# interface_board.net
KiCad netlist of a schematic drawn in EAGLE
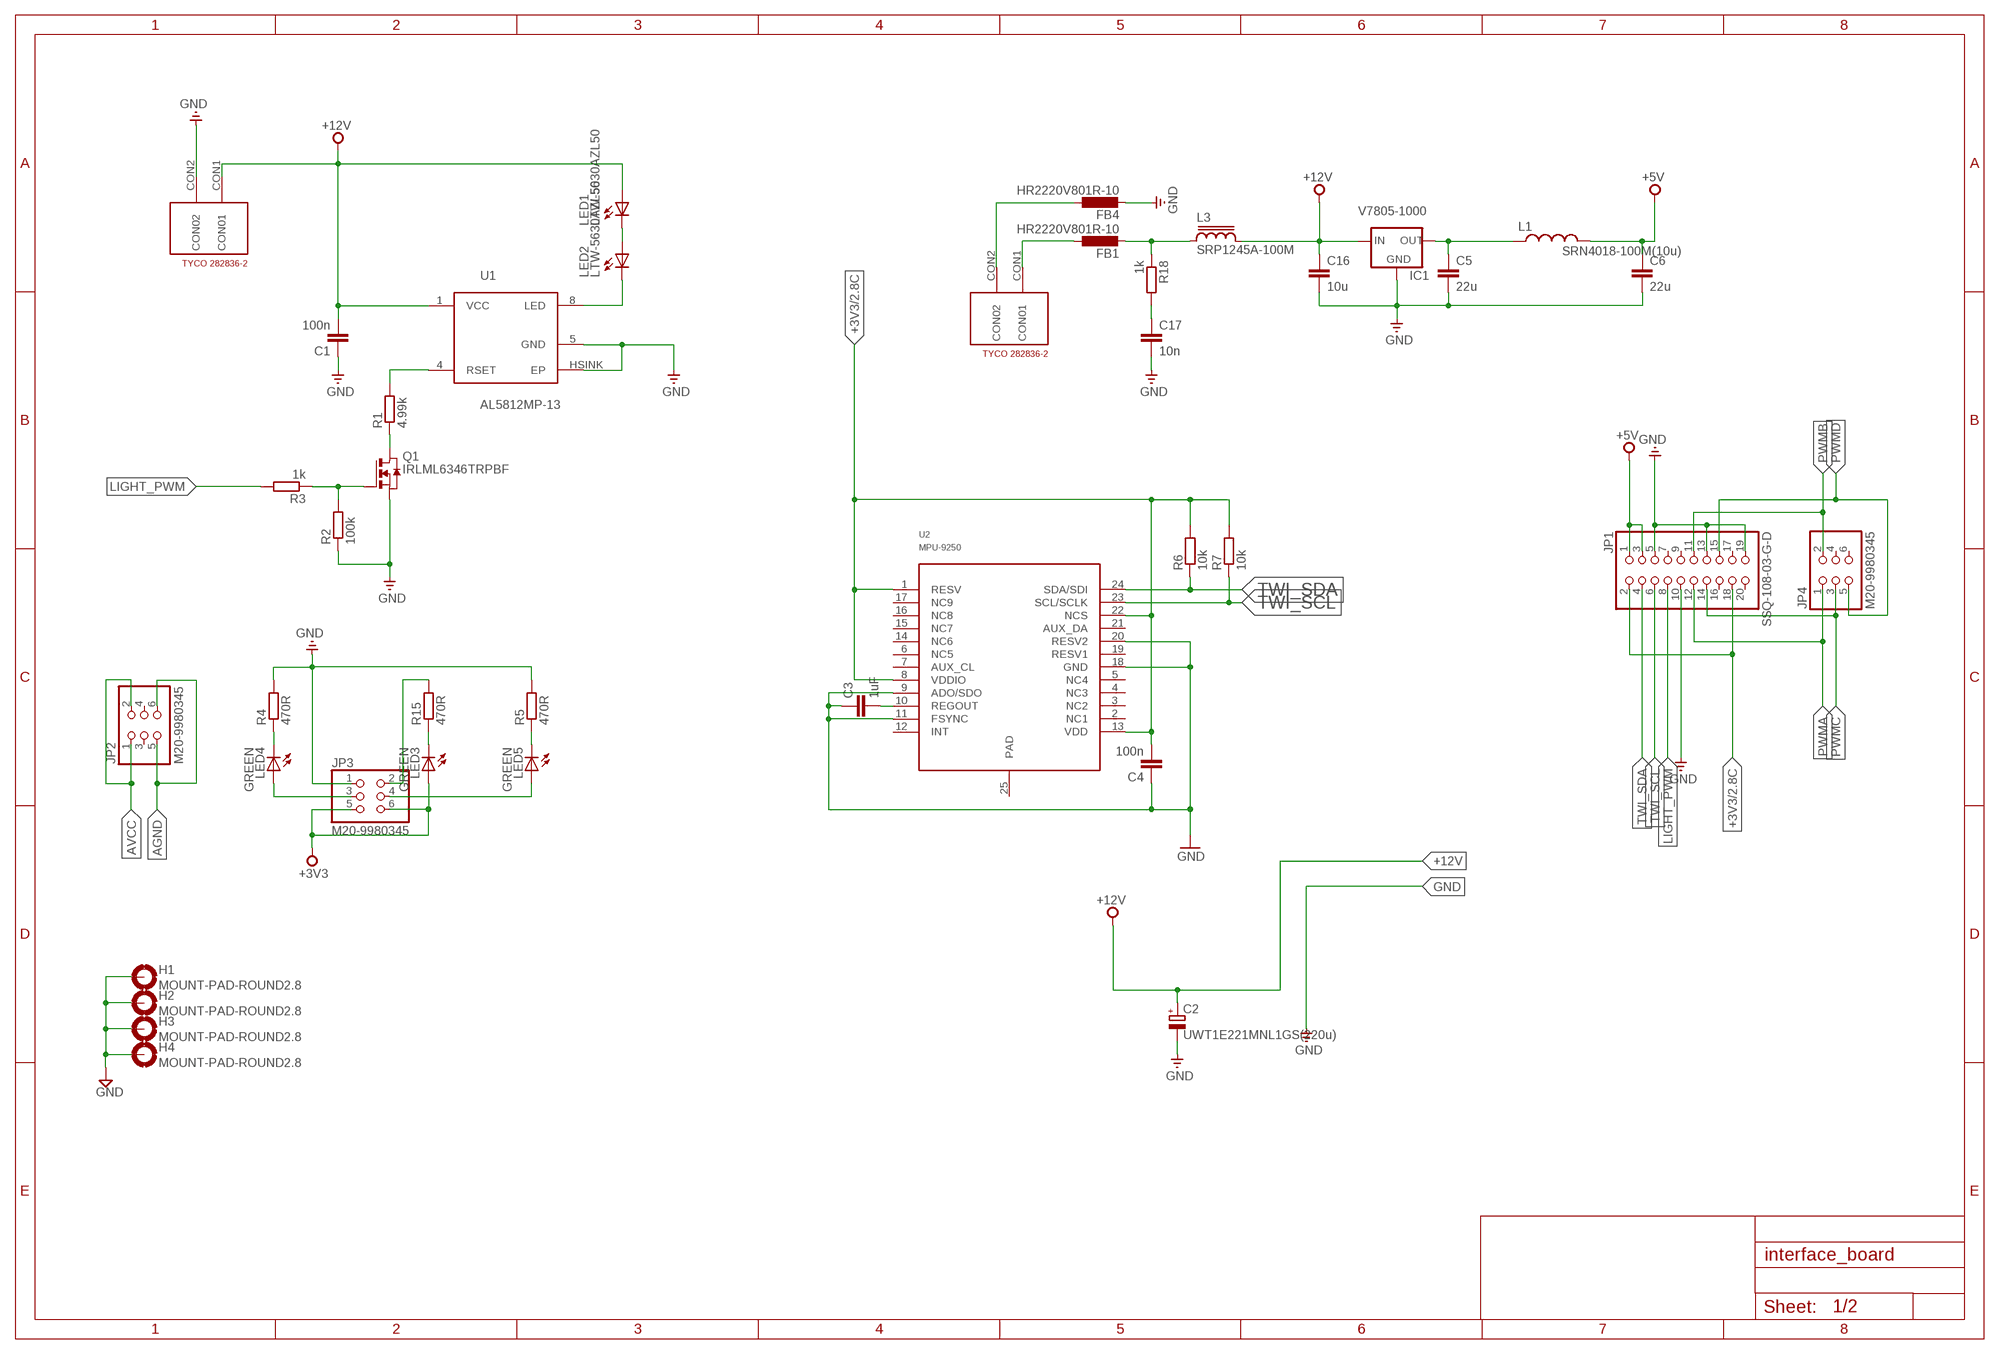
[diagram p0: schematic, sheet 1]
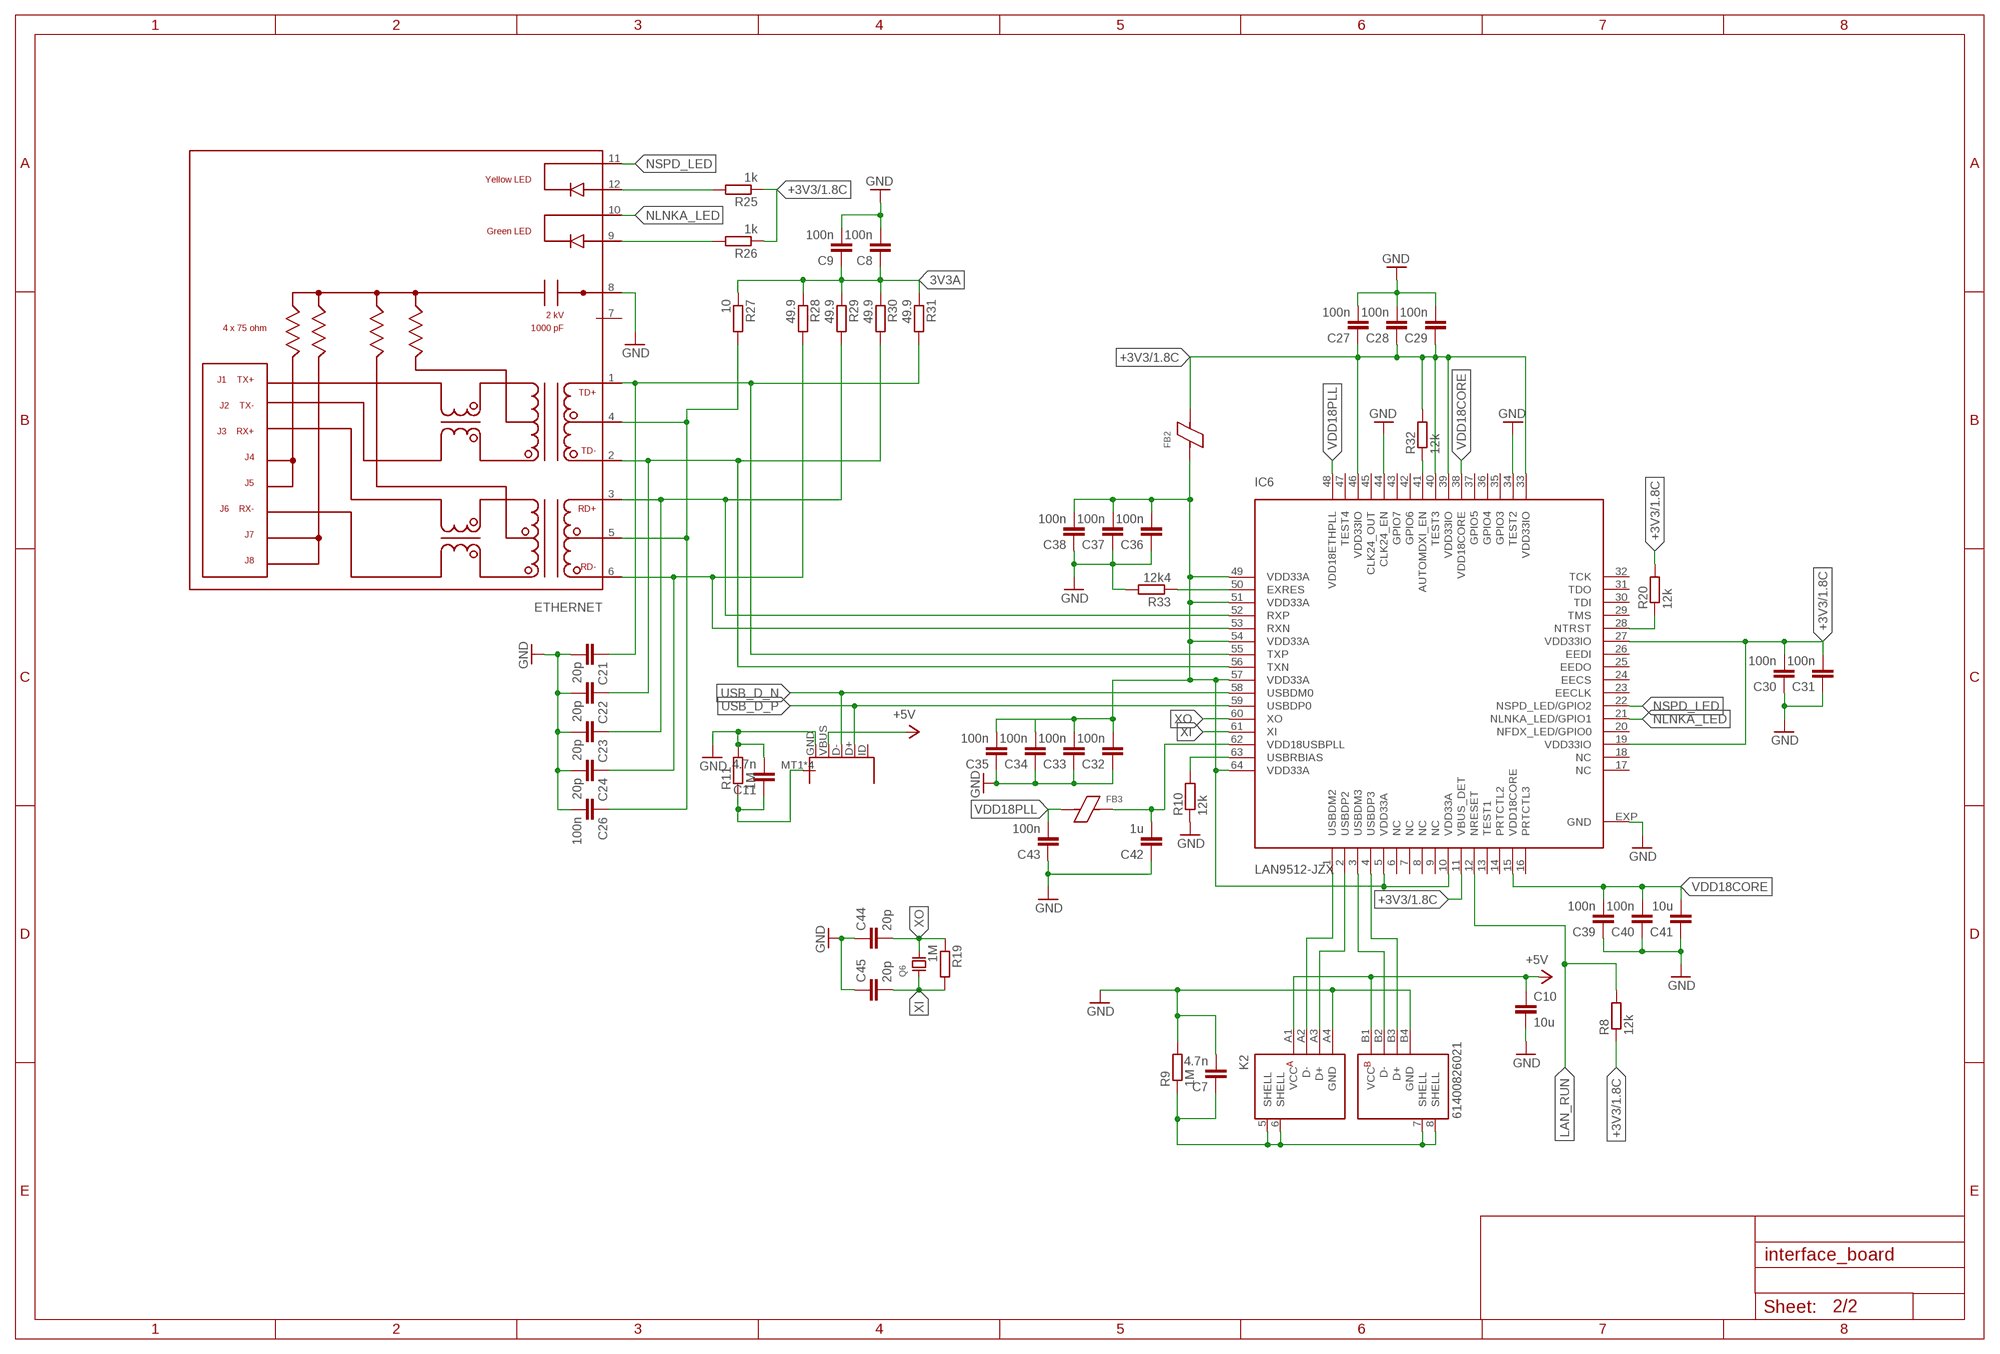
[diagram p1: schematic, sheet 2]

(export (version "E")
  (design (tool "Eeschema 10.0.6"))
  (components
    (comp (ref "C7")
      (value "4.7n")
      (footprint "eagle-import:C0402")
      (libsource (lib "eagle-import") (part "C-EUC0402"))
    )
    (comp (ref "C8")
      (value "100n")
      (footprint "eagle-import:C0402")
      (libsource (lib "eagle-import") (part "C-EUC0402"))
    )
    (comp (ref "C9")
      (value "100n")
      (footprint "eagle-import:C0402")
      (libsource (lib "eagle-import") (part "C-EUC0402"))
    )
    (comp (ref "C10")
      (value "10u")
      (footprint "eagle-import:C0603")
      (libsource (lib "eagle-import") (part "C-EUC0603"))
    )
    (comp (ref "C11")
      (value "4.7n")
      (footprint "eagle-import:C0402")
      (libsource (lib "eagle-import") (part "C-EUC0402"))
    )
    (comp (ref "C21")
      (value "20p")
      (footprint "eagle-import:C0402")
      (libsource (lib "eagle-import") (part "C-EUC0402"))
    )
    (comp (ref "C22")
      (value "20p")
      (footprint "eagle-import:C0402")
      (libsource (lib "eagle-import") (part "C-EUC0402"))
    )
    (comp (ref "C23")
      (value "20p")
      (footprint "eagle-import:C0402")
      (libsource (lib "eagle-import") (part "C-EUC0402"))
    )
    (comp (ref "C24")
      (value "20p")
      (footprint "eagle-import:C0402")
      (libsource (lib "eagle-import") (part "C-EUC0402"))
    )
    (comp (ref "C26")
      (value "100n")
      (footprint "eagle-import:C0402")
      (libsource (lib "eagle-import") (part "C-EUC0402"))
    )
    (comp (ref "C27")
      (value "100n")
      (footprint "eagle-import:C0402")
      (libsource (lib "eagle-import") (part "C-EUC0402"))
    )
    (comp (ref "C28")
      (value "100n")
      (footprint "eagle-import:C0402")
      (libsource (lib "eagle-import") (part "C-EUC0402"))
    )
    (comp (ref "C29")
      (value "100n")
      (footprint "eagle-import:C0402")
      (libsource (lib "eagle-import") (part "C-EUC0402"))
    )
    (comp (ref "C30")
      (value "100n")
      (footprint "eagle-import:C0402")
      (libsource (lib "eagle-import") (part "C-EUC0402"))
    )
    (comp (ref "C31")
      (value "100n")
      (footprint "eagle-import:C0402")
      (libsource (lib "eagle-import") (part "C-EUC0402"))
    )
    (comp (ref "C32")
      (value "100n")
      (footprint "eagle-import:C0402")
      (libsource (lib "eagle-import") (part "C-EUC0402"))
    )
    (comp (ref "C33")
      (value "100n")
      (footprint "eagle-import:C0402")
      (libsource (lib "eagle-import") (part "C-EUC0402"))
    )
    (comp (ref "C34")
      (value "100n")
      (footprint "eagle-import:C0402")
      (libsource (lib "eagle-import") (part "C-EUC0402"))
    )
    (comp (ref "C35")
      (value "100n")
      (footprint "eagle-import:C0402")
      (libsource (lib "eagle-import") (part "C-EUC0402"))
    )
    (comp (ref "C36")
      (value "100n")
      (footprint "eagle-import:C0402")
      (libsource (lib "eagle-import") (part "C-EUC0402"))
    )
    (comp (ref "C37")
      (value "100n")
      (footprint "eagle-import:C0402")
      (libsource (lib "eagle-import") (part "C-EUC0402"))
    )
    (comp (ref "C38")
      (value "100n")
      (footprint "eagle-import:C0402")
      (libsource (lib "eagle-import") (part "C-EUC0402"))
    )
    (comp (ref "C39")
      (value "100n")
      (footprint "eagle-import:C0402")
      (libsource (lib "eagle-import") (part "C-EUC0402"))
    )
    (comp (ref "C40")
      (value "100n")
      (footprint "eagle-import:C0402")
      (libsource (lib "eagle-import") (part "C-EUC0402"))
    )
    (comp (ref "C41")
      (value "10u")
      (footprint "eagle-import:C0603")
      (libsource (lib "eagle-import") (part "C-EUC0603"))
    )
    (comp (ref "C42")
      (value "1u")
      (footprint "eagle-import:C0402")
      (libsource (lib "eagle-import") (part "C-EUC0402"))
    )
    (comp (ref "C43")
      (value "100n")
      (footprint "eagle-import:C0402")
      (libsource (lib "eagle-import") (part "C-EUC0402"))
    )
    (comp (ref "C44")
      (value "20p")
      (footprint "eagle-import:C0402")
      (libsource (lib "eagle-import") (part "C-EUC0402"))
    )
    (comp (ref "C45")
      (value "20p")
      (footprint "eagle-import:C0402")
      (libsource (lib "eagle-import") (part "C-EUC0402"))
    )
    (comp (ref "ETHERNET")
      (value "HR911105A")
      (footprint "eagle-import:RJ45")
      (libsource (lib "eagle-import") (part "HR911105A"))
    )
    (comp (ref "FB2")
      (value "742792022")
      (footprint "eagle-import:C0805")
      (libsource (lib "eagle-import") (part "FERRITE_BEAD"))
    )
    (comp (ref "FB3")
      (value "742792022")
      (footprint "eagle-import:C0805")
      (libsource (lib "eagle-import") (part "FERRITE_BEAD"))
    )
    (comp (ref "IC6")
      (value "LAN9512-JZX")
      (footprint "eagle-import:QFN64-9X9")
      (libsource (lib "eagle-import") (part "LAN9512"))
    )
    (comp (ref "JP6")
      (value "10118192-0001LF")
      (footprint "eagle-import:USB-MICRO")
      (libsource (lib "eagle-import") (part "USB-IDMICRO"))
    )
    (comp (ref "K2")
      (value "61400826021")
      (footprint "eagle-import:61400826021")
      (libsource (lib "eagle-import") (part "61400826021"))
    )
    (comp (ref "Q6")
      (value "FA-238 25.0000MB")
      (footprint "eagle-import:CTS_32X25")
      (libsource (lib "eagle-import") (part "CTS_32X25_SMD"))
    )
    (comp (ref "R8")
      (value "12k")
      (footprint "eagle-import:R0402")
      (libsource (lib "eagle-import") (part "R-EU_R0402"))
    )
    (comp (ref "R9")
      (value "1M")
      (footprint "eagle-import:R0402")
      (libsource (lib "eagle-import") (part "R-EU_R0402"))
    )
    (comp (ref "R10")
      (value "12k")
      (footprint "eagle-import:R0402")
      (libsource (lib "eagle-import") (part "R-EU_R0402"))
    )
    (comp (ref "R11")
      (value "1M")
      (footprint "eagle-import:R0402")
      (libsource (lib "eagle-import") (part "R-EU_R0402"))
    )
    (comp (ref "R19")
      (value "1M")
      (footprint "eagle-import:R0402")
      (libsource (lib "eagle-import") (part "R-EU_R0402"))
    )
    (comp (ref "R20")
      (value "12k")
      (footprint "eagle-import:R0402")
      (libsource (lib "eagle-import") (part "R-EU_R0402"))
    )
    (comp (ref "R25")
      (value "1k")
      (footprint "eagle-import:R0402")
      (libsource (lib "eagle-import") (part "R-EU_R0402"))
    )
    (comp (ref "R26")
      (value "1k")
      (footprint "eagle-import:R0402")
      (libsource (lib "eagle-import") (part "R-EU_R0402"))
    )
    (comp (ref "R27")
      (value "10")
      (footprint "eagle-import:R0402")
      (libsource (lib "eagle-import") (part "R-EU_R0402"))
    )
    (comp (ref "R28")
      (value "49.9")
      (footprint "eagle-import:R0402")
      (libsource (lib "eagle-import") (part "R-EU_R0402"))
    )
    (comp (ref "R29")
      (value "49.9")
      (footprint "eagle-import:R0402")
      (libsource (lib "eagle-import") (part "R-EU_R0402"))
    )
    (comp (ref "R30")
      (value "49.9")
      (footprint "eagle-import:R0402")
      (libsource (lib "eagle-import") (part "R-EU_R0402"))
    )
    (comp (ref "R31")
      (value "49.9")
      (footprint "eagle-import:R0402")
      (libsource (lib "eagle-import") (part "R-EU_R0402"))
    )
    (comp (ref "R32")
      (value "12k")
      (footprint "eagle-import:R0402")
      (libsource (lib "eagle-import") (part "R-EU_R0402"))
    )
    (comp (ref "R33")
      (value "12k4")
      (footprint "eagle-import:R0402")
      (libsource (lib "eagle-import") (part "R-EU_R0402"))
    )
    (comp (ref "C1")
      (value "100n")
      (footprint "eagle-import:C0402")
      (libsource (lib "eagle-import") (part "C-EUC0402"))
    )
    (comp (ref "C2")
      (value "UWT1E221MNL1GS(220u)")
      (footprint "eagle-import:153CLV-0810")
      (libsource (lib "eagle-import") (part "CPOL-EU153CLV-0810"))
    )
    (comp (ref "C3")
      (value "1uF")
      (footprint "eagle-import:C0402")
      (libsource (lib "eagle-import") (part "C-EUC0402"))
    )
    (comp (ref "C4")
      (value "100n")
      (footprint "eagle-import:C0402")
      (libsource (lib "eagle-import") (part "C-EUC0402"))
    )
    (comp (ref "C5")
      (value "22u")
      (footprint "eagle-import:C0603")
      (libsource (lib "eagle-import") (part "C-EUC0603"))
    )
    (comp (ref "C6")
      (value "22u")
      (footprint "eagle-import:C0603")
      (libsource (lib "eagle-import") (part "C-EUC0603"))
    )
    (comp (ref "C16")
      (value "10u")
      (footprint "eagle-import:C0603")
      (libsource (lib "eagle-import") (part "C-EUC0603"))
    )
    (comp (ref "C17")
      (value "10n")
      (footprint "eagle-import:C0402")
      (libsource (lib "eagle-import") (part "C-EUC0402"))
    )
    (comp (ref "FB1")
      (value "HR2220V801R-10")
      (footprint "eagle-import:L5650M")
      (libsource (lib "eagle-import") (part "L-EUL5650M"))
    )
    (comp (ref "FB4")
      (value "HR2220V801R-10")
      (footprint "eagle-import:L5650M")
      (libsource (lib "eagle-import") (part "L-EUL5650M"))
    )
    (comp (ref "H1")
      (value "MOUNT-PAD-ROUND2.8")
      (footprint "eagle-import:2,8-PAD")
      (libsource (lib "eagle-import") (part "MOUNT-PAD-ROUND2.8"))
    )
    (comp (ref "H2")
      (value "MOUNT-PAD-ROUND2.8")
      (footprint "eagle-import:2,8-PAD")
      (libsource (lib "eagle-import") (part "MOUNT-PAD-ROUND2.8"))
    )
    (comp (ref "H3")
      (value "MOUNT-PAD-ROUND2.8")
      (footprint "eagle-import:2,8-PAD")
      (libsource (lib "eagle-import") (part "MOUNT-PAD-ROUND2.8"))
    )
    (comp (ref "H4")
      (value "MOUNT-PAD-ROUND2.8")
      (footprint "eagle-import:2,8-PAD")
      (libsource (lib "eagle-import") (part "MOUNT-PAD-ROUND2.8"))
    )
    (comp (ref "IC1")
      (value "V7805-1000")
      (footprint "eagle-import:DIP_3PIN")
      (libsource (lib "eagle-import") (part "VR_1OUTXX"))
    )
    (comp (ref "JP1")
      (value "SSQ-108-03-G-D")
      (footprint "eagle-import:2X10")
      (libsource (lib "eagle-import") (part "PINHD-2X10"))
    )
    (comp (ref "JP2")
      (value "M20-9980345")
      (footprint "eagle-import:2X03")
      (libsource (lib "eagle-import") (part "PINHD-2X3"))
    )
    (comp (ref "JP3")
      (value "M20-9980345")
      (footprint "eagle-import:2X03")
      (libsource (lib "eagle-import") (part "PINHD-2X3"))
    )
    (comp (ref "JP4")
      (value "M20-9980345")
      (footprint "eagle-import:2X03")
      (libsource (lib "eagle-import") (part "PINHD-2X3"))
    )
    (comp (ref "L1")
      (value "SRN4018-100M(10u)")
      (footprint "eagle-import:BOURNS-SRN4018")
      (libsource (lib "eagle-import") (part "BOURNS-SRN4018"))
    )
    (comp (ref "L3")
      (value "SRP1245A-100M")
      (footprint "eagle-import:SRP1250A")
      (libsource (lib "eagle-import") (part "SRP1250A"))
    )
    (comp (ref "LED1")
      (value "LTW-5630AZL50")
      (footprint "eagle-import:LITEON-5630")
      (libsource (lib "eagle-import") (part "LTW-5630AZL"))
    )
    (comp (ref "LED2")
      (value "LTW-5630AZL50")
      (footprint "eagle-import:LITEON-5630")
      (libsource (lib "eagle-import") (part "LTW-5630AZL"))
    )
    (comp (ref "LED3")
      (value "GREEN")
      (footprint "eagle-import:CHIP-LED0603")
      (libsource (lib "eagle-import") (part "LEDCHIP-LED0603"))
    )
    (comp (ref "LED4")
      (value "GREEN")
      (footprint "eagle-import:CHIP-LED0603")
      (libsource (lib "eagle-import") (part "LEDCHIP-LED0603"))
    )
    (comp (ref "LED5")
      (value "GREEN")
      (footprint "eagle-import:CHIP-LED0603")
      (libsource (lib "eagle-import") (part "LEDCHIP-LED0603"))
    )
    (comp (ref "Q1")
      (value "IRLML6346TRPBF")
      (footprint "eagle-import:SOT23")
      (libsource (lib "eagle-import") (part "NMOS-FETSOT23"))
    )
    (comp (ref "R1")
      (value "4.99k")
      (footprint "eagle-import:R0402")
      (libsource (lib "eagle-import") (part "R-EU_R0402"))
    )
    (comp (ref "R2")
      (value "100k")
      (footprint "eagle-import:R0402")
      (libsource (lib "eagle-import") (part "R-EU_R0402"))
    )
    (comp (ref "R3")
      (value "1k")
      (footprint "eagle-import:R0402")
      (libsource (lib "eagle-import") (part "R-EU_R0402"))
    )
    (comp (ref "R4")
      (value "470R")
      (footprint "eagle-import:R0402")
      (libsource (lib "eagle-import") (part "R-EU_R0402"))
    )
    (comp (ref "R5")
      (value "470R")
      (footprint "eagle-import:R0402")
      (libsource (lib "eagle-import") (part "R-EU_R0402"))
    )
    (comp (ref "R6")
      (value "10k")
      (footprint "eagle-import:R0402")
      (libsource (lib "eagle-import") (part "R-EU_R0402"))
    )
    (comp (ref "R7")
      (value "10k")
      (footprint "eagle-import:R0402")
      (libsource (lib "eagle-import") (part "R-EU_R0402"))
    )
    (comp (ref "R15")
      (value "470R")
      (footprint "eagle-import:R0402")
      (libsource (lib "eagle-import") (part "R-EU_R0402"))
    )
    (comp (ref "R18")
      (value "1k")
      (footprint "eagle-import:R0402")
      (libsource (lib "eagle-import") (part "R-EU_R0402"))
    )
    (comp (ref "U$2")
      (value "282836-2")
      (footprint "eagle-import:282836-2")
      (libsource (lib "eagle-import") (part "282836-2"))
    )
    (comp (ref "U$4")
      (value "282836-2")
      (footprint "eagle-import:282836-2")
      (libsource (lib "eagle-import") (part "282836-2"))
    )
    (comp (ref "U1")
      (value "AL5812MP-13")
      (footprint "eagle-import:MSOP-8EP")
      (libsource (lib "eagle-import") (part "AL5812MP-13"))
    )
    (comp (ref "U2")
      (value "MPU-9250")
      (footprint "eagle-import:LEAD-QFN24")
      (libsource (lib "eagle-import") (part "MPU-9250"))
    )
  )
  (nets
    (net (code "1") (name "+3V3") (class "Default")
      (node (ref "C27") (pin "1") (pinfunction "1_1") (pintype "passive"))
      (node (ref "C28") (pin "1") (pinfunction "1_1") (pintype "passive"))
      (node (ref "C29") (pin "1") (pinfunction "1_1") (pintype "passive"))
      (node (ref "C30") (pin "2") (pinfunction "2_2") (pintype "passive"))
      (node (ref "C31") (pin "2") (pinfunction "2_2") (pintype "passive"))
      (node (ref "C4") (pin "2") (pinfunction "2_2") (pintype "passive"))
      (node (ref "FB2") (pin "2") (pinfunction "P$2_2") (pintype "bidirectional"))
      (node (ref "IC6") (pin "11") (pinfunction "VBUS_DET_11") (pintype "bidirectional"))
      (node (ref "IC6") (pin "19") (pinfunction "VDD33IO_19") (pintype "bidirectional"))
      (node (ref "IC6") (pin "27") (pinfunction "VDD33IO_27") (pintype "bidirectional"))
      (node (ref "IC6") (pin "33") (pinfunction "VDD33IO_33") (pintype "bidirectional"))
      (node (ref "IC6") (pin "39") (pinfunction "VDD33IO_39") (pintype "bidirectional"))
      (node (ref "IC6") (pin "40") (pinfunction "TEST3_40") (pintype "bidirectional"))
      (node (ref "IC6") (pin "46") (pinfunction "VDD33IO_46") (pintype "bidirectional"))
      (node (ref "JP1") (pin "18") (pinfunction "18_18") (pintype "passive"))
      (node (ref "JP1") (pin "2") (pinfunction "2_2") (pintype "passive"))
      (node (ref "JP3") (pin "5") (pinfunction "5_5") (pintype "passive"))
      (node (ref "JP3") (pin "6") (pinfunction "6_6") (pintype "passive"))
      (node (ref "LED3") (pin "A") (pinfunction "A_A") (pintype "passive"))
      (node (ref "R20") (pin "2") (pinfunction "2_2") (pintype "passive"))
      (node (ref "R25") (pin "1") (pinfunction "1_1") (pintype "passive"))
      (node (ref "R26") (pin "1") (pinfunction "1_1") (pintype "passive"))
      (node (ref "R32") (pin "2") (pinfunction "2_2") (pintype "passive"))
      (node (ref "R6") (pin "2") (pinfunction "2_2") (pintype "passive"))
      (node (ref "R7") (pin "2") (pinfunction "2_2") (pintype "passive"))
      (node (ref "R8") (pin "1") (pinfunction "1_1") (pintype "passive"))
      (node (ref "U2") (pin "1") (pinfunction "RESV_1") (pintype "bidirectional"))
      (node (ref "U2") (pin "13") (pinfunction "VDD_13") (pintype "bidirectional"))
      (node (ref "U2") (pin "22") (pinfunction "NCS_22") (pintype "bidirectional"))
      (node (ref "U2") (pin "8") (pinfunction "VDDIO_8") (pintype "bidirectional"))
    )
    (net (code "2") (name "+5V") (class "Default")
      (node (ref "C10") (pin "1") (pinfunction "1_1") (pintype "passive"))
      (node (ref "C6") (pin "1") (pinfunction "1_1") (pintype "passive"))
      (node (ref "JP1") (pin "1") (pinfunction "1_1") (pintype "passive"))
      (node (ref "JP1") (pin "3") (pinfunction "3_3") (pintype "passive"))
      (node (ref "JP6") (pin "VBUS") (pinfunction "VBUS_VBUS") (pintype "bidirectional"))
      (node (ref "K2") (pin "A1") (pinfunction "VCC_A1") (pintype "bidirectional"))
      (node (ref "K2") (pin "B1") (pinfunction "VCC_B1") (pintype "bidirectional"))
      (node (ref "L1") (pin "P$1") (pinfunction "1_P$1") (pintype "passive"))
    )
    (net (code "3") (name "+12V") (class "Default")
      (node (ref "C1") (pin "2") (pinfunction "2_2") (pintype "passive"))
      (node (ref "C16") (pin "1") (pinfunction "1_1") (pintype "passive"))
      (node (ref "C2") (pin "+") (pinfunction "+_+") (pintype "passive"))
      (node (ref "IC1") (pin "IN") (pinfunction "IN_IN") (pintype "input"))
      (node (ref "L3") (pin "2") (pinfunction "2_2") (pintype "passive"))
      (node (ref "LED1") (pin "A1") (pinfunction "A_A1") (pintype "passive"))
      (node (ref "LED1") (pin "A2") (pinfunction "A_A2") (pintype "passive"))
      (node (ref "LED1") (pin "A3") (pinfunction "A_A3") (pintype "passive"))
      (node (ref "U$4") (pin "CON1") (pinfunction "CON01_CON1") (pintype "bidirectional"))
      (node (ref "U1") (pin "1") (pinfunction "VCC_1") (pintype "bidirectional"))
    )
    (net (code "4") (name "3V3A") (class "Default")
      (node (ref "C32") (pin "2") (pinfunction "2_2") (pintype "passive"))
      (node (ref "C33") (pin "2") (pinfunction "2_2") (pintype "passive"))
      (node (ref "C34") (pin "2") (pinfunction "2_2") (pintype "passive"))
      (node (ref "C35") (pin "2") (pinfunction "2_2") (pintype "passive"))
      (node (ref "C36") (pin "2") (pinfunction "2_2") (pintype "passive"))
      (node (ref "C37") (pin "2") (pinfunction "2_2") (pintype "passive"))
      (node (ref "C38") (pin "2") (pinfunction "2_2") (pintype "passive"))
      (node (ref "C8") (pin "1") (pinfunction "1_1") (pintype "passive"))
      (node (ref "C9") (pin "1") (pinfunction "1_1") (pintype "passive"))
      (node (ref "FB2") (pin "1") (pinfunction "P$1_1") (pintype "bidirectional"))
      (node (ref "IC6") (pin "10") (pinfunction "VDD33A_10") (pintype "bidirectional"))
      (node (ref "IC6") (pin "49") (pinfunction "VDD33A_49") (pintype "bidirectional"))
      (node (ref "IC6") (pin "5") (pinfunction "VDD33A_5") (pintype "bidirectional"))
      (node (ref "IC6") (pin "51") (pinfunction "VDD33A_51") (pintype "bidirectional"))
      (node (ref "IC6") (pin "54") (pinfunction "VDD33A_54") (pintype "bidirectional"))
      (node (ref "IC6") (pin "57") (pinfunction "VDD33A_57") (pintype "bidirectional"))
      (node (ref "IC6") (pin "64") (pinfunction "VDD33A_64") (pintype "bidirectional"))
      (node (ref "R27") (pin "1") (pinfunction "1_1") (pintype "passive"))
      (node (ref "R28") (pin "1") (pinfunction "1_1") (pintype "passive"))
      (node (ref "R29") (pin "1") (pinfunction "1_1") (pintype "passive"))
      (node (ref "R30") (pin "1") (pinfunction "1_1") (pintype "passive"))
      (node (ref "R31") (pin "1") (pinfunction "1_1") (pintype "passive"))
    )
    (net (code "5") (name "AGND") (class "Default")
      (node (ref "FB4") (pin "1") (pinfunction "1_1") (pintype "passive"))
      (node (ref "JP2") (pin "5") (pinfunction "5_5") (pintype "passive"))
      (node (ref "JP2") (pin "6") (pinfunction "6_6") (pintype "passive"))
      (node (ref "U$2") (pin "CON2") (pinfunction "CON02_CON2") (pintype "bidirectional"))
    )
    (net (code "6") (name "AVCC") (class "Default")
      (node (ref "FB1") (pin "1") (pinfunction "1_1") (pintype "passive"))
      (node (ref "JP2") (pin "1") (pinfunction "1_1") (pintype "passive"))
      (node (ref "JP2") (pin "2") (pinfunction "2_2") (pintype "passive"))
      (node (ref "U$2") (pin "CON1") (pinfunction "CON01_CON1") (pintype "bidirectional"))
    )
    (net (code "7") (name "GND") (class "Default")
      (node (ref "C1") (pin "1") (pinfunction "1_1") (pintype "passive"))
      (node (ref "C10") (pin "2") (pinfunction "2_2") (pintype "passive"))
      (node (ref "C11") (pin "2") (pinfunction "2_2") (pintype "passive"))
      (node (ref "C16") (pin "2") (pinfunction "2_2") (pintype "passive"))
      (node (ref "C17") (pin "2") (pinfunction "2_2") (pintype "passive"))
      (node (ref "C2") (pin "-") (pinfunction "-_-") (pintype "passive"))
      (node (ref "C21") (pin "2") (pinfunction "2_2") (pintype "passive"))
      (node (ref "C22") (pin "2") (pinfunction "2_2") (pintype "passive"))
      (node (ref "C23") (pin "2") (pinfunction "2_2") (pintype "passive"))
      (node (ref "C24") (pin "2") (pinfunction "2_2") (pintype "passive"))
      (node (ref "C26") (pin "2") (pinfunction "2_2") (pintype "passive"))
      (node (ref "C27") (pin "2") (pinfunction "2_2") (pintype "passive"))
      (node (ref "C28") (pin "2") (pinfunction "2_2") (pintype "passive"))
      (node (ref "C29") (pin "2") (pinfunction "2_2") (pintype "passive"))
      (node (ref "C3") (pin "1") (pinfunction "1_1") (pintype "passive"))
      (node (ref "C30") (pin "1") (pinfunction "1_1") (pintype "passive"))
      (node (ref "C31") (pin "1") (pinfunction "1_1") (pintype "passive"))
      (node (ref "C32") (pin "1") (pinfunction "1_1") (pintype "passive"))
      (node (ref "C33") (pin "1") (pinfunction "1_1") (pintype "passive"))
      (node (ref "C34") (pin "1") (pinfunction "1_1") (pintype "passive"))
      (node (ref "C35") (pin "1") (pinfunction "1_1") (pintype "passive"))
      (node (ref "C36") (pin "1") (pinfunction "1_1") (pintype "passive"))
      (node (ref "C37") (pin "1") (pinfunction "1_1") (pintype "passive"))
      (node (ref "C38") (pin "1") (pinfunction "1_1") (pintype "passive"))
      (node (ref "C39") (pin "1") (pinfunction "1_1") (pintype "passive"))
      (node (ref "C4") (pin "1") (pinfunction "1_1") (pintype "passive"))
      (node (ref "C40") (pin "1") (pinfunction "1_1") (pintype "passive"))
      (node (ref "C41") (pin "1") (pinfunction "1_1") (pintype "passive"))
      (node (ref "C42") (pin "1") (pinfunction "1_1") (pintype "passive"))
      (node (ref "C43") (pin "1") (pinfunction "1_1") (pintype "passive"))
      (node (ref "C44") (pin "1") (pinfunction "1_1") (pintype "passive"))
      (node (ref "C45") (pin "1") (pinfunction "1_1") (pintype "passive"))
      (node (ref "C5") (pin "2") (pinfunction "2_2") (pintype "passive"))
      (node (ref "C6") (pin "2") (pinfunction "2_2") (pintype "passive"))
      (node (ref "C7") (pin "2") (pinfunction "2_2") (pintype "passive"))
      (node (ref "C8") (pin "2") (pinfunction "2_2") (pintype "passive"))
      (node (ref "C9") (pin "2") (pinfunction "2_2") (pintype "passive"))
      (node (ref "ETHERNET") (pin "8") (pinfunction "P$8_8") (pintype "bidirectional"))
      (node (ref "FB4") (pin "2") (pinfunction "2_2") (pintype "passive"))
      (node (ref "H1") (pin "B2,8") (pinfunction "MOUNT_B2,8") (pintype "passive"))
      (node (ref "H2") (pin "B2,8") (pinfunction "MOUNT_B2,8") (pintype "passive"))
      (node (ref "H3") (pin "B2,8") (pinfunction "MOUNT_B2,8") (pintype "passive"))
      (node (ref "H4") (pin "B2,8") (pinfunction "MOUNT_B2,8") (pintype "passive"))
      (node (ref "IC1") (pin "GND") (pinfunction "GND_GND") (pintype "input"))
      (node (ref "IC6") (pin "34") (pinfunction "TEST2_34") (pintype "bidirectional"))
      (node (ref "IC6") (pin "44") (pinfunction "CLK24_EN_44") (pintype "bidirectional"))
      (node (ref "IC6") (pin "EXP") (pinfunction "GND_EXP") (pintype "bidirectional"))
      (node (ref "JP1") (pin "10") (pinfunction "10_10") (pintype "passive"))
      (node (ref "JP1") (pin "13") (pinfunction "13_13") (pintype "passive"))
      (node (ref "JP1") (pin "19") (pinfunction "19_19") (pintype "passive"))
      (node (ref "JP1") (pin "5") (pinfunction "5_5") (pintype "passive"))
      (node (ref "JP3") (pin "1") (pinfunction "1_1") (pintype "passive"))
      (node (ref "JP6") (pin "GND") (pinfunction "GND_GND") (pintype "bidirectional"))
      (node (ref "K2") (pin "A4") (pinfunction "GND_A4") (pintype "bidirectional"))
      (node (ref "K2") (pin "B4") (pinfunction "GND_B4") (pintype "bidirectional"))
      (node (ref "Q1") (pin "2") (pinfunction "S_2") (pintype "passive"))
      (node (ref "R10") (pin "1") (pinfunction "1_1") (pintype "passive"))
      (node (ref "R11") (pin "2") (pinfunction "2_2") (pintype "passive"))
      (node (ref "R2") (pin "1") (pinfunction "1_1") (pintype "passive"))
      (node (ref "R33") (pin "2") (pinfunction "2_2") (pintype "passive"))
      (node (ref "R4") (pin "2") (pinfunction "2_2") (pintype "passive"))
      (node (ref "R5") (pin "2") (pinfunction "2_2") (pintype "passive"))
      (node (ref "R9") (pin "2") (pinfunction "2_2") (pintype "passive"))
      (node (ref "U$4") (pin "CON2") (pinfunction "CON02_CON2") (pintype "bidirectional"))
      (node (ref "U1") (pin "5") (pinfunction "GND_5") (pintype "bidirectional"))
      (node (ref "U1") (pin "HSINK") (pinfunction "EP_HSINK") (pintype "bidirectional"))
      (node (ref "U2") (pin "11") (pinfunction "FSYNC_11") (pintype "bidirectional"))
      (node (ref "U2") (pin "18") (pinfunction "GND_18") (pintype "bidirectional"))
      (node (ref "U2") (pin "20") (pinfunction "RESV2_20") (pintype "bidirectional"))
      (node (ref "U2") (pin "9") (pinfunction "ADO/SDO_9") (pintype "bidirectional"))
    )
    (net (code "8") (name "LAN_RUN") (class "Default")
      (node (ref "IC6") (pin "12") (pinfunction "NRESET_12") (pintype "bidirectional"))
      (node (ref "R8") (pin "2") (pinfunction "2_2") (pintype "passive"))
    )
    (net (code "9") (name "LIGHT_PWM") (class "Default")
      (node (ref "JP1") (pin "8") (pinfunction "8_8") (pintype "passive"))
      (node (ref "R3") (pin "2") (pinfunction "2_2") (pintype "passive"))
    )
    (net (code "10") (name "NLNKA_LED") (class "Default")
      (node (ref "ETHERNET") (pin "10") (pinfunction "P$10_10") (pintype "bidirectional"))
      (node (ref "IC6") (pin "21") (pinfunction "NLNKA_LED/GPIO1_21") (pintype "bidirectional"))
    )
    (net (code "11") (name "NSPD_LED") (class "Default")
      (node (ref "ETHERNET") (pin "11") (pinfunction "P$11_11") (pintype "bidirectional"))
      (node (ref "IC6") (pin "22") (pinfunction "NSPD_LED/GPIO2_22") (pintype "bidirectional"))
    )
    (net (code "12") (name "Net-(C7-Pad1)") (class "Default")
      (node (ref "C7") (pin "1") (pinfunction "1_1") (pintype "passive"))
      (node (ref "K2") (pin "5") (pinfunction "SHELL_5") (pintype "bidirectional"))
      (node (ref "K2") (pin "6") (pinfunction "SHELL_6") (pintype "bidirectional"))
      (node (ref "K2") (pin "7") (pinfunction "SHELL_7") (pintype "bidirectional"))
      (node (ref "K2") (pin "8") (pinfunction "SHELL_8") (pintype "bidirectional"))
      (node (ref "R9") (pin "1") (pinfunction "1_1") (pintype "passive"))
    )
    (net (code "13") (name "Net-(C11-Pad1)") (class "Default")
      (node (ref "C11") (pin "1") (pinfunction "1_1") (pintype "passive"))
      (node (ref "JP6") (pin "MT1") (pinfunction "SHELL_MT1") (pintype "bidirectional"))
      (node (ref "JP6") (pin "MT2") (pinfunction "SHELL_MT2") (pintype "bidirectional"))
      (node (ref "JP6") (pin "P$1") (pinfunction "SHELL_P$1") (pintype "bidirectional"))
      (node (ref "JP6") (pin "P$2") (pinfunction "SHELL_P$2") (pintype "bidirectional"))
      (node (ref "R11") (pin "1") (pinfunction "1_1") (pintype "passive"))
    )
    (net (code "14") (name "Net-(C17-Pad1)") (class "Default")
      (node (ref "C17") (pin "1") (pinfunction "1_1") (pintype "passive"))
      (node (ref "R18") (pin "2") (pinfunction "2_2") (pintype "passive"))
    )
    (net (code "15") (name "Net-(ETHERNET-P$1)") (class "Default")
      (node (ref "C21") (pin "1") (pinfunction "1_1") (pintype "passive"))
      (node (ref "ETHERNET") (pin "1") (pinfunction "P$1_1") (pintype "bidirectional"))
      (node (ref "IC6") (pin "55") (pinfunction "TXP_55") (pintype "bidirectional"))
      (node (ref "R31") (pin "2") (pinfunction "2_2") (pintype "passive"))
    )
    (net (code "16") (name "Net-(ETHERNET-P$2)") (class "Default")
      (node (ref "C22") (pin "1") (pinfunction "1_1") (pintype "passive"))
      (node (ref "ETHERNET") (pin "2") (pinfunction "P$2_2") (pintype "bidirectional"))
      (node (ref "IC6") (pin "56") (pinfunction "TXN_56") (pintype "bidirectional"))
      (node (ref "R30") (pin "2") (pinfunction "2_2") (pintype "passive"))
    )
    (net (code "17") (name "Net-(ETHERNET-P$3)") (class "Default")
      (node (ref "C23") (pin "1") (pinfunction "1_1") (pintype "passive"))
      (node (ref "ETHERNET") (pin "3") (pinfunction "P$3_3") (pintype "bidirectional"))
      (node (ref "IC6") (pin "52") (pinfunction "RXP_52") (pintype "bidirectional"))
      (node (ref "R29") (pin "2") (pinfunction "2_2") (pintype "passive"))
    )
    (net (code "18") (name "Net-(ETHERNET-P$4)") (class "Default")
      (node (ref "C26") (pin "1") (pinfunction "1_1") (pintype "passive"))
      (node (ref "ETHERNET") (pin "4") (pinfunction "P$4_4") (pintype "bidirectional"))
      (node (ref "ETHERNET") (pin "5") (pinfunction "P$5_5") (pintype "bidirectional"))
      (node (ref "R27") (pin "2") (pinfunction "2_2") (pintype "passive"))
    )
    (net (code "19") (name "Net-(ETHERNET-P$6)") (class "Default")
      (node (ref "C24") (pin "1") (pinfunction "1_1") (pintype "passive"))
      (node (ref "ETHERNET") (pin "6") (pinfunction "P$6_6") (pintype "bidirectional"))
      (node (ref "IC6") (pin "53") (pinfunction "RXN_53") (pintype "bidirectional"))
      (node (ref "R28") (pin "2") (pinfunction "2_2") (pintype "passive"))
    )
    (net (code "20") (name "Net-(ETHERNET-P$9)") (class "Default")
      (node (ref "ETHERNET") (pin "9") (pinfunction "P$9_9") (pintype "bidirectional"))
      (node (ref "R26") (pin "2") (pinfunction "2_2") (pintype "passive"))
    )
    (net (code "21") (name "Net-(ETHERNET-P$12)") (class "Default")
      (node (ref "ETHERNET") (pin "12") (pinfunction "P$12_12") (pintype "bidirectional"))
      (node (ref "R25") (pin "2") (pinfunction "2_2") (pintype "passive"))
    )
    (net (code "22") (name "Net-(FB1-Pad2)") (class "Default")
      (node (ref "FB1") (pin "2") (pinfunction "2_2") (pintype "passive"))
      (node (ref "L3") (pin "1") (pinfunction "1_1") (pintype "passive"))
      (node (ref "R18") (pin "1") (pinfunction "1_1") (pintype "passive"))
    )
    (net (code "23") (name "Net-(FB3-P$2)") (class "Default")
      (node (ref "C42") (pin "2") (pinfunction "2_2") (pintype "passive"))
      (node (ref "FB3") (pin "2") (pinfunction "P$2_2") (pintype "bidirectional"))
      (node (ref "IC6") (pin "62") (pinfunction "VDD18USBPLL_62") (pintype "bidirectional"))
    )
    (net (code "24") (name "Net-(IC6-AUTOMDXI_EN)") (class "Default")
      (node (ref "IC6") (pin "41") (pinfunction "AUTOMDXI_EN_41") (pintype "bidirectional"))
      (node (ref "R32") (pin "1") (pinfunction "1_1") (pintype "passive"))
    )
    (net (code "25") (name "Net-(IC6-EXRES)") (class "Default")
      (node (ref "IC6") (pin "50") (pinfunction "EXRES_50") (pintype "bidirectional"))
      (node (ref "R33") (pin "1") (pinfunction "1_1") (pintype "passive"))
    )
    (net (code "26") (name "Net-(IC6-NTRST)") (class "Default")
      (node (ref "IC6") (pin "28") (pinfunction "NTRST_28") (pintype "bidirectional"))
      (node (ref "R20") (pin "1") (pinfunction "1_1") (pintype "passive"))
    )
    (net (code "27") (name "Net-(IC6-USBDM2)") (class "Default")
      (node (ref "IC6") (pin "1") (pinfunction "USBDM2_1") (pintype "bidirectional"))
      (node (ref "K2") (pin "A2") (pinfunction "D-_A2") (pintype "bidirectional"))
    )
    (net (code "28") (name "Net-(IC6-USBDM3)") (class "Default")
      (node (ref "IC6") (pin "3") (pinfunction "USBDM3_3") (pintype "bidirectional"))
      (node (ref "K2") (pin "B2") (pinfunction "D-_B2") (pintype "bidirectional"))
    )
    (net (code "29") (name "Net-(IC6-USBDP2)") (class "Default")
      (node (ref "IC6") (pin "2") (pinfunction "USBDP2_2") (pintype "bidirectional"))
      (node (ref "K2") (pin "A3") (pinfunction "D+_A3") (pintype "bidirectional"))
    )
    (net (code "30") (name "Net-(IC6-USBDP3)") (class "Default")
      (node (ref "IC6") (pin "4") (pinfunction "USBDP3_4") (pintype "bidirectional"))
      (node (ref "K2") (pin "B3") (pinfunction "D+_B3") (pintype "bidirectional"))
    )
    (net (code "31") (name "Net-(IC6-USBRBIAS)") (class "Default")
      (node (ref "IC6") (pin "63") (pinfunction "USBRBIAS_63") (pintype "bidirectional"))
      (node (ref "R10") (pin "2") (pinfunction "2_2") (pintype "passive"))
    )
    (net (code "32") (name "Net-(JP3-Pad2)") (class "Default")
      (node (ref "JP3") (pin "2") (pinfunction "2_2") (pintype "passive"))
      (node (ref "R15") (pin "2") (pinfunction "2_2") (pintype "passive"))
    )
    (net (code "33") (name "Net-(JP3-Pad3)") (class "Default")
      (node (ref "JP3") (pin "3") (pinfunction "3_3") (pintype "passive"))
      (node (ref "LED4") (pin "A") (pinfunction "A_A") (pintype "passive"))
    )
    (net (code "34") (name "Net-(JP3-Pad4)") (class "Default")
      (node (ref "JP3") (pin "4") (pinfunction "4_4") (pintype "passive"))
      (node (ref "LED5") (pin "A") (pinfunction "A_A") (pintype "passive"))
    )
    (net (code "35") (name "Net-(L1-2)") (class "Default")
      (node (ref "C5") (pin "1") (pinfunction "1_1") (pintype "passive"))
      (node (ref "IC1") (pin "OUT") (pinfunction "OUT_OUT") (pintype "passive"))
      (node (ref "L1") (pin "P$2") (pinfunction "2_P$2") (pintype "passive"))
    )
    (net (code "36") (name "Net-(LED1-C-PadC1)") (class "Default")
      (node (ref "LED1") (pin "C1") (pinfunction "C_C1") (pintype "passive"))
      (node (ref "LED1") (pin "C2") (pinfunction "C_C2") (pintype "passive"))
      (node (ref "LED2") (pin "A1") (pinfunction "A_A1") (pintype "passive"))
      (node (ref "LED2") (pin "A2") (pinfunction "A_A2") (pintype "passive"))
      (node (ref "LED2") (pin "A3") (pinfunction "A_A3") (pintype "passive"))
    )
    (net (code "37") (name "Net-(LED3-PadC)") (class "Default")
      (node (ref "LED3") (pin "C") (pinfunction "C_C") (pintype "passive"))
      (node (ref "R15") (pin "1") (pinfunction "1_1") (pintype "passive"))
    )
    (net (code "38") (name "Net-(LED4-PadC)") (class "Default")
      (node (ref "LED4") (pin "C") (pinfunction "C_C") (pintype "passive"))
      (node (ref "R4") (pin "1") (pinfunction "1_1") (pintype "passive"))
    )
    (net (code "39") (name "Net-(LED5-PadC)") (class "Default")
      (node (ref "LED5") (pin "C") (pinfunction "C_C") (pintype "passive"))
      (node (ref "R5") (pin "1") (pinfunction "1_1") (pintype "passive"))
    )
    (net (code "40") (name "Net-(Q1-D)") (class "Default")
      (node (ref "Q1") (pin "3") (pinfunction "D_3") (pintype "passive"))
      (node (ref "R1") (pin "1") (pinfunction "1_1") (pintype "passive"))
    )
    (net (code "41") (name "Net-(Q1-G)") (class "Default")
      (node (ref "Q1") (pin "1") (pinfunction "G_1") (pintype "passive"))
      (node (ref "R2") (pin "2") (pinfunction "2_2") (pintype "passive"))
      (node (ref "R3") (pin "1") (pinfunction "1_1") (pintype "passive"))
    )
    (net (code "42") (name "Net-(U1-LED)") (class "Default")
      (node (ref "LED2") (pin "C1") (pinfunction "C_C1") (pintype "passive"))
      (node (ref "LED2") (pin "C2") (pinfunction "C_C2") (pintype "passive"))
      (node (ref "U1") (pin "8") (pinfunction "LED_8") (pintype "bidirectional"))
    )
    (net (code "43") (name "Net-(U1-RSET)") (class "Default")
      (node (ref "R1") (pin "2") (pinfunction "2_2") (pintype "passive"))
      (node (ref "U1") (pin "4") (pinfunction "RSET_4") (pintype "bidirectional"))
    )
    (net (code "44") (name "Net-(U2-REGOUT)") (class "Default")
      (node (ref "C3") (pin "2") (pinfunction "2_2") (pintype "passive"))
      (node (ref "U2") (pin "10") (pinfunction "REGOUT_10") (pintype "bidirectional"))
    )
    (net (code "45") (name "PWMA") (class "Default")
      (node (ref "JP1") (pin "12") (pinfunction "12_12") (pintype "passive"))
      (node (ref "JP4") (pin "1") (pinfunction "1_1") (pintype "passive"))
    )
    (net (code "46") (name "PWMB") (class "Default")
      (node (ref "JP1") (pin "11") (pinfunction "11_11") (pintype "passive"))
      (node (ref "JP4") (pin "2") (pinfunction "2_2") (pintype "passive"))
    )
    (net (code "47") (name "PWMC") (class "Default")
      (node (ref "JP1") (pin "14") (pinfunction "14_14") (pintype "passive"))
      (node (ref "JP4") (pin "3") (pinfunction "3_3") (pintype "passive"))
    )
    (net (code "48") (name "PWMD") (class "Default")
      (node (ref "JP1") (pin "15") (pinfunction "15_15") (pintype "passive"))
      (node (ref "JP4") (pin "5") (pinfunction "5_5") (pintype "passive"))
    )
    (net (code "49") (name "TWI_SCL") (class "Default")
      (node (ref "JP1") (pin "6") (pinfunction "6_6") (pintype "passive"))
      (node (ref "R7") (pin "1") (pinfunction "1_1") (pintype "passive"))
      (node (ref "U2") (pin "23") (pinfunction "SCL/SCLK_23") (pintype "bidirectional"))
    )
    (net (code "50") (name "TWI_SDA") (class "Default")
      (node (ref "JP1") (pin "4") (pinfunction "4_4") (pintype "passive"))
      (node (ref "R6") (pin "1") (pinfunction "1_1") (pintype "passive"))
      (node (ref "U2") (pin "24") (pinfunction "SDA/SDI_24") (pintype "bidirectional"))
    )
    (net (code "51") (name "USB_D_N") (class "Default")
      (node (ref "IC6") (pin "58") (pinfunction "USBDM0_58") (pintype "bidirectional"))
      (node (ref "JP6") (pin "D-") (pinfunction "D-_D-") (pintype "bidirectional"))
    )
    (net (code "52") (name "USB_D_P") (class "Default")
      (node (ref "IC6") (pin "59") (pinfunction "USBDP0_59") (pintype "bidirectional"))
      (node (ref "JP6") (pin "D+") (pinfunction "D+_D+") (pintype "bidirectional"))
    )
    (net (code "53") (name "VDD18CORE") (class "Default")
      (node (ref "C39") (pin "2") (pinfunction "2_2") (pintype "passive"))
      (node (ref "C40") (pin "2") (pinfunction "2_2") (pintype "passive"))
      (node (ref "C41") (pin "2") (pinfunction "2_2") (pintype "passive"))
      (node (ref "IC6") (pin "15") (pinfunction "VDD18CORE_15") (pintype "bidirectional"))
      (node (ref "IC6") (pin "38") (pinfunction "VDD18CORE_38") (pintype "bidirectional"))
    )
    (net (code "54") (name "VDD18PLL") (class "Default")
      (node (ref "C43") (pin "2") (pinfunction "2_2") (pintype "passive"))
      (node (ref "FB3") (pin "1") (pinfunction "P$1_1") (pintype "bidirectional"))
      (node (ref "IC6") (pin "48") (pinfunction "VDD18ETHPLL_48") (pintype "bidirectional"))
    )
    (net (code "55") (name "XI") (class "Default")
      (node (ref "C45") (pin "2") (pinfunction "2_2") (pintype "passive"))
      (node (ref "IC6") (pin "61") (pinfunction "XI_61") (pintype "bidirectional"))
      (node (ref "Q6") (pin "1") (pinfunction "X1_1") (pintype "bidirectional"))
      (node (ref "R19") (pin "2") (pinfunction "2_2") (pintype "passive"))
    )
    (net (code "56") (name "XO") (class "Default")
      (node (ref "C44") (pin "2") (pinfunction "2_2") (pintype "passive"))
      (node (ref "IC6") (pin "60") (pinfunction "XO_60") (pintype "bidirectional"))
      (node (ref "Q6") (pin "3") (pinfunction "X2_3") (pintype "bidirectional"))
      (node (ref "R19") (pin "1") (pinfunction "1_1") (pintype "passive"))
    )
    (net (code "57") (name "unconnected-(ETHERNET-P$7-Pad7)") (class "Default")
      (node (ref "ETHERNET") (pin "7") (pinfunction "P$7_7") (pintype "bidirectional"))
    )
    (net (code "58") (name "unconnected-(IC6-CLK24_OUT-Pad45)") (class "Default")
      (node (ref "IC6") (pin "45") (pinfunction "CLK24_OUT_45") (pintype "bidirectional"))
    )
    (net (code "59") (name "unconnected-(IC6-EECLK-Pad23)") (class "Default")
      (node (ref "IC6") (pin "23") (pinfunction "EECLK_23") (pintype "bidirectional"))
    )
    (net (code "60") (name "unconnected-(IC6-EECS-Pad24)") (class "Default")
      (node (ref "IC6") (pin "24") (pinfunction "EECS_24") (pintype "bidirectional"))
    )
    (net (code "61") (name "unconnected-(IC6-EEDI-Pad26)") (class "Default")
      (node (ref "IC6") (pin "26") (pinfunction "EEDI_26") (pintype "bidirectional"))
    )
    (net (code "62") (name "unconnected-(IC6-EEDO-Pad25)") (class "Default")
      (node (ref "IC6") (pin "25") (pinfunction "EEDO_25") (pintype "bidirectional"))
    )
    (net (code "63") (name "unconnected-(IC6-GPIO3-Pad35)") (class "Default")
      (node (ref "IC6") (pin "35") (pinfunction "GPIO3_35") (pintype "bidirectional"))
    )
    (net (code "64") (name "unconnected-(IC6-GPIO4-Pad36)") (class "Default")
      (node (ref "IC6") (pin "36") (pinfunction "GPIO4_36") (pintype "bidirectional"))
    )
    (net (code "65") (name "unconnected-(IC6-GPIO5-Pad37)") (class "Default")
      (node (ref "IC6") (pin "37") (pinfunction "GPIO5_37") (pintype "bidirectional"))
    )
    (net (code "66") (name "unconnected-(IC6-GPIO6-Pad42)") (class "Default")
      (node (ref "IC6") (pin "42") (pinfunction "GPIO6_42") (pintype "bidirectional"))
    )
    (net (code "67") (name "unconnected-(IC6-GPIO7-Pad43)") (class "Default")
      (node (ref "IC6") (pin "43") (pinfunction "GPIO7_43") (pintype "bidirectional"))
    )
    (net (code "68") (name "unconnected-(IC6-NC-Pad6)") (class "Default")
      (node (ref "IC6") (pin "6") (pinfunction "NC_6") (pintype "bidirectional"))
    )
    (net (code "69") (name "unconnected-(IC6-NC-Pad7)") (class "Default")
      (node (ref "IC6") (pin "7") (pinfunction "NC_7") (pintype "bidirectional"))
    )
    (net (code "70") (name "unconnected-(IC6-NC-Pad8)") (class "Default")
      (node (ref "IC6") (pin "8") (pinfunction "NC_8") (pintype "bidirectional"))
    )
    (net (code "71") (name "unconnected-(IC6-NC-Pad9)") (class "Default")
      (node (ref "IC6") (pin "9") (pinfunction "NC_9") (pintype "bidirectional"))
    )
    (net (code "72") (name "unconnected-(IC6-NC-Pad17)") (class "Default")
      (node (ref "IC6") (pin "17") (pinfunction "NC_17") (pintype "bidirectional"))
    )
    (net (code "73") (name "unconnected-(IC6-NC-Pad18)") (class "Default")
      (node (ref "IC6") (pin "18") (pinfunction "NC_18") (pintype "bidirectional"))
    )
    (net (code "74") (name "unconnected-(IC6-NFDX_LED{slash}GPIO0-Pad20)") (class "Default")
      (node (ref "IC6") (pin "20") (pinfunction "NFDX_LED/GPIO0_20") (pintype "bidirectional"))
    )
    (net (code "75") (name "unconnected-(IC6-PRTCTL2-Pad14)") (class "Default")
      (node (ref "IC6") (pin "14") (pinfunction "PRTCTL2_14") (pintype "bidirectional"))
    )
    (net (code "76") (name "unconnected-(IC6-PRTCTL3-Pad16)") (class "Default")
      (node (ref "IC6") (pin "16") (pinfunction "PRTCTL3_16") (pintype "bidirectional"))
    )
    (net (code "77") (name "unconnected-(IC6-TCK-Pad32)") (class "Default")
      (node (ref "IC6") (pin "32") (pinfunction "TCK_32") (pintype "bidirectional"))
    )
    (net (code "78") (name "unconnected-(IC6-TDI-Pad30)") (class "Default")
      (node (ref "IC6") (pin "30") (pinfunction "TDI_30") (pintype "bidirectional"))
    )
    (net (code "79") (name "unconnected-(IC6-TDO-Pad31)") (class "Default")
      (node (ref "IC6") (pin "31") (pinfunction "TDO_31") (pintype "bidirectional"))
    )
    (net (code "80") (name "unconnected-(IC6-TEST1-Pad13)") (class "Default")
      (node (ref "IC6") (pin "13") (pinfunction "TEST1_13") (pintype "bidirectional"))
    )
    (net (code "81") (name "unconnected-(IC6-TEST4-Pad47)") (class "Default")
      (node (ref "IC6") (pin "47") (pinfunction "TEST4_47") (pintype "bidirectional"))
    )
    (net (code "82") (name "unconnected-(IC6-TMS-Pad29)") (class "Default")
      (node (ref "IC6") (pin "29") (pinfunction "TMS_29") (pintype "bidirectional"))
    )
    (net (code "83") (name "unconnected-(JP1-Pad7)") (class "Default")
      (node (ref "JP1") (pin "7") (pinfunction "7_7") (pintype "passive"))
    )
    (net (code "84") (name "unconnected-(JP1-Pad9)") (class "Default")
      (node (ref "JP1") (pin "9") (pinfunction "9_9") (pintype "passive"))
    )
    (net (code "85") (name "unconnected-(JP1-Pad16)") (class "Default")
      (node (ref "JP1") (pin "16") (pinfunction "16_16") (pintype "passive"))
    )
    (net (code "86") (name "unconnected-(JP1-Pad17)") (class "Default")
      (node (ref "JP1") (pin "17") (pinfunction "17_17") (pintype "passive"))
    )
    (net (code "87") (name "unconnected-(JP1-Pad20)") (class "Default")
      (node (ref "JP1") (pin "20") (pinfunction "20_20") (pintype "passive"))
    )
    (net (code "88") (name "unconnected-(JP2-Pad3)") (class "Default")
      (node (ref "JP2") (pin "3") (pinfunction "3_3") (pintype "passive"))
    )
    (net (code "89") (name "unconnected-(JP2-Pad4)") (class "Default")
      (node (ref "JP2") (pin "4") (pinfunction "4_4") (pintype "passive"))
    )
    (net (code "90") (name "unconnected-(JP4-Pad4)") (class "Default")
      (node (ref "JP4") (pin "4") (pinfunction "4_4") (pintype "passive"))
    )
    (net (code "91") (name "unconnected-(JP4-Pad6)") (class "Default")
      (node (ref "JP4") (pin "6") (pinfunction "6_6") (pintype "passive"))
    )
    (net (code "92") (name "unconnected-(JP6-PadID)") (class "Default")
      (node (ref "JP6") (pin "ID") (pinfunction "ID_ID") (pintype "bidirectional"))
    )
    (net (code "93") (name "unconnected-(U2-AUX_CL-Pad7)") (class "Default")
      (node (ref "U2") (pin "7") (pinfunction "AUX_CL_7") (pintype "bidirectional"))
    )
    (net (code "94") (name "unconnected-(U2-AUX_DA-Pad21)") (class "Default")
      (node (ref "U2") (pin "21") (pinfunction "AUX_DA_21") (pintype "bidirectional"))
    )
    (net (code "95") (name "unconnected-(U2-INT-Pad12)") (class "Default")
      (node (ref "U2") (pin "12") (pinfunction "INT_12") (pintype "bidirectional"))
    )
    (net (code "96") (name "unconnected-(U2-NC1-Pad2)") (class "Default")
      (node (ref "U2") (pin "2") (pinfunction "NC1_2") (pintype "bidirectional"))
    )
    (net (code "97") (name "unconnected-(U2-NC2-Pad3)") (class "Default")
      (node (ref "U2") (pin "3") (pinfunction "NC2_3") (pintype "bidirectional"))
    )
    (net (code "98") (name "unconnected-(U2-NC3-Pad4)") (class "Default")
      (node (ref "U2") (pin "4") (pinfunction "NC3_4") (pintype "bidirectional"))
    )
    (net (code "99") (name "unconnected-(U2-NC4-Pad5)") (class "Default")
      (node (ref "U2") (pin "5") (pinfunction "NC4_5") (pintype "bidirectional"))
    )
    (net (code "100") (name "unconnected-(U2-NC5-Pad6)") (class "Default")
      (node (ref "U2") (pin "6") (pinfunction "NC5_6") (pintype "bidirectional"))
    )
    (net (code "101") (name "unconnected-(U2-NC6-Pad14)") (class "Default")
      (node (ref "U2") (pin "14") (pinfunction "NC6_14") (pintype "bidirectional"))
    )
    (net (code "102") (name "unconnected-(U2-NC7-Pad15)") (class "Default")
      (node (ref "U2") (pin "15") (pinfunction "NC7_15") (pintype "bidirectional"))
    )
    (net (code "103") (name "unconnected-(U2-NC8-Pad16)") (class "Default")
      (node (ref "U2") (pin "16") (pinfunction "NC8_16") (pintype "bidirectional"))
    )
    (net (code "104") (name "unconnected-(U2-NC9-Pad17)") (class "Default")
      (node (ref "U2") (pin "17") (pinfunction "NC9_17") (pintype "bidirectional"))
    )
    (net (code "105") (name "unconnected-(U2-PAD-Pad25)") (class "Default")
      (node (ref "U2") (pin "25") (pinfunction "PAD_25") (pintype "bidirectional"))
    )
    (net (code "106") (name "unconnected-(U2-RESV1-Pad19)") (class "Default")
      (node (ref "U2") (pin "19") (pinfunction "RESV1_19") (pintype "bidirectional"))
    )
  )
)
